# CrashButtonESP8266.net
KiCad netlist of a schematic drawn in EAGLE
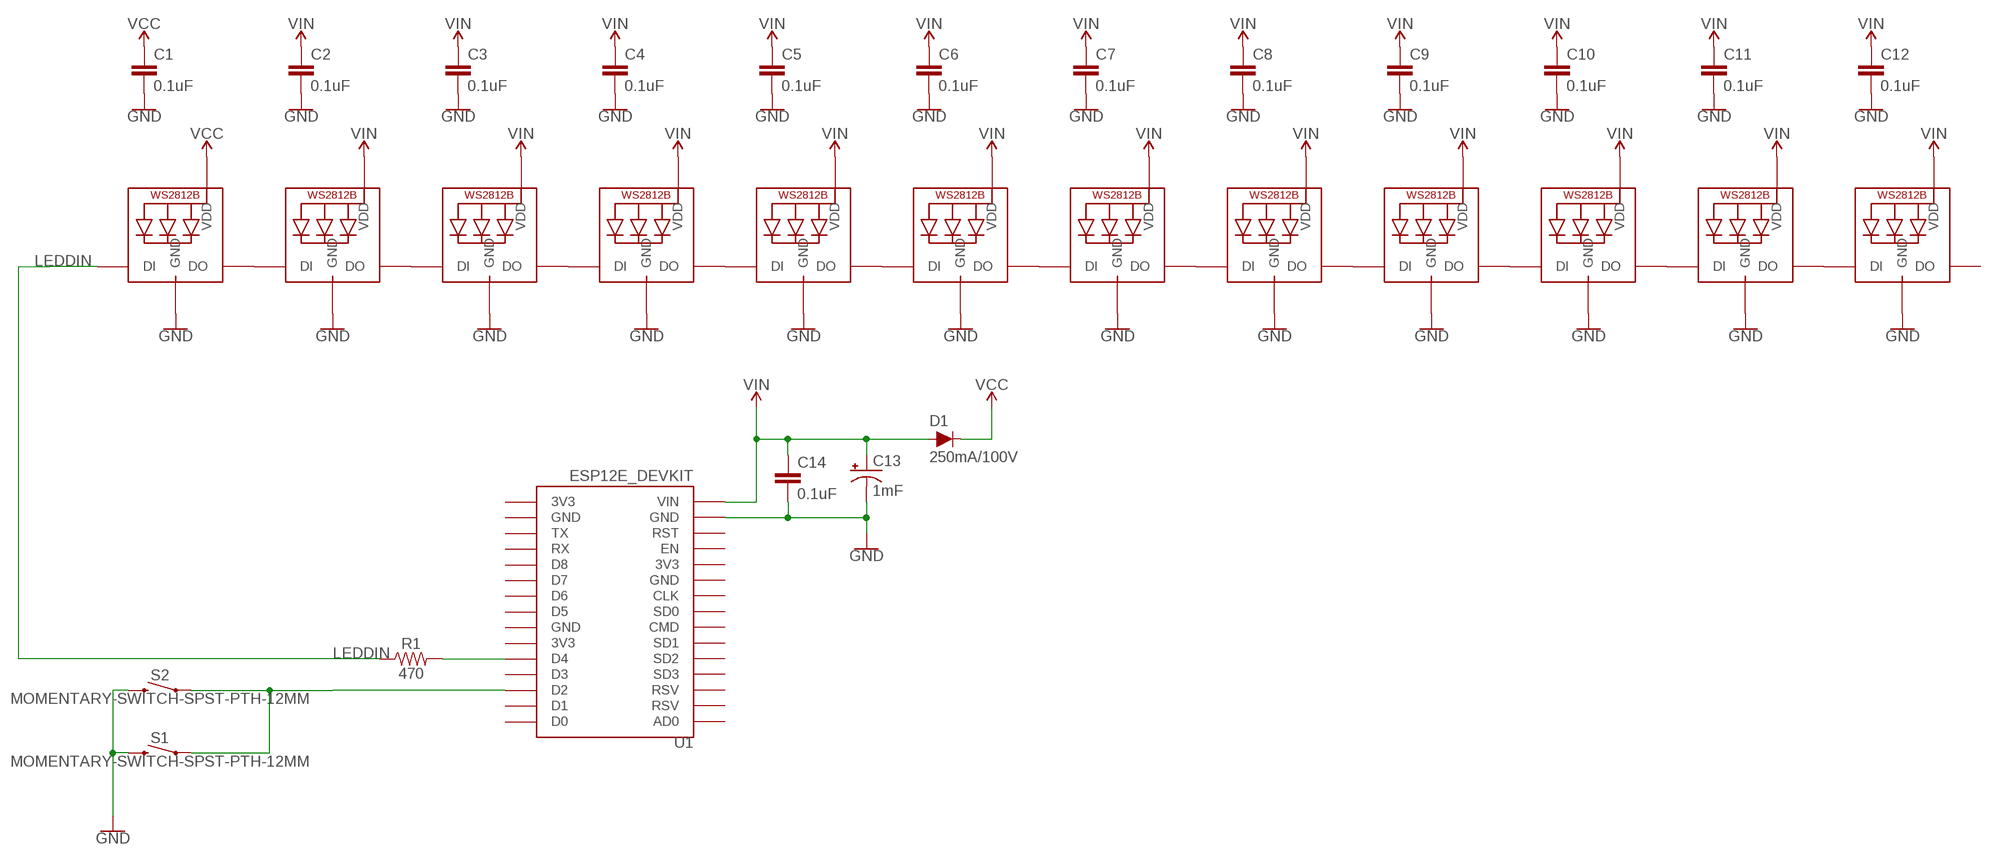
[diagram p0: schematic, sheet 1]

(export (version "E")
  (design (tool "Eeschema 10.0.6"))
  (components
    (comp (ref "C1")
      (value "0.1uF")
      (footprint "eagle-import:0603")
      (libsource (lib "eagle-import") (part "0.1UF-0603-25V-(+80/-20%)"))
    )
    (comp (ref "C2")
      (value "0.1uF")
      (footprint "eagle-import:0603")
      (libsource (lib "eagle-import") (part "0.1UF-0603-25V-(+80/-20%)"))
    )
    (comp (ref "C3")
      (value "0.1uF")
      (footprint "eagle-import:0603")
      (libsource (lib "eagle-import") (part "0.1UF-0603-25V-(+80/-20%)"))
    )
    (comp (ref "C4")
      (value "0.1uF")
      (footprint "eagle-import:0603")
      (libsource (lib "eagle-import") (part "0.1UF-0603-25V-(+80/-20%)"))
    )
    (comp (ref "C5")
      (value "0.1uF")
      (footprint "eagle-import:0603")
      (libsource (lib "eagle-import") (part "0.1UF-0603-25V-(+80/-20%)"))
    )
    (comp (ref "C6")
      (value "0.1uF")
      (footprint "eagle-import:0603")
      (libsource (lib "eagle-import") (part "0.1UF-0603-25V-(+80/-20%)"))
    )
    (comp (ref "C7")
      (value "0.1uF")
      (footprint "eagle-import:0603")
      (libsource (lib "eagle-import") (part "0.1UF-0603-25V-(+80/-20%)"))
    )
    (comp (ref "C8")
      (value "0.1uF")
      (footprint "eagle-import:0603")
      (libsource (lib "eagle-import") (part "0.1UF-0603-25V-(+80/-20%)"))
    )
    (comp (ref "C9")
      (value "0.1uF")
      (footprint "eagle-import:0603")
      (libsource (lib "eagle-import") (part "0.1UF-0603-25V-(+80/-20%)"))
    )
    (comp (ref "C10")
      (value "0.1uF")
      (footprint "eagle-import:0603")
      (libsource (lib "eagle-import") (part "0.1UF-0603-25V-(+80/-20%)"))
    )
    (comp (ref "C11")
      (value "0.1uF")
      (footprint "eagle-import:0603")
      (libsource (lib "eagle-import") (part "0.1UF-0603-25V-(+80/-20%)"))
    )
    (comp (ref "C12")
      (value "0.1uF")
      (footprint "eagle-import:0603")
      (libsource (lib "eagle-import") (part "0.1UF-0603-25V-(+80/-20%)"))
    )
    (comp (ref "C13")
      (value "1mF")
      (footprint "eagle-import:CPOL-RADIAL-5MM-10MM")
      (libsource (lib "eagle-import") (part "1000UF-RADIAL-5MM-25V-20%"))
    )
    (comp (ref "C14")
      (value "0.1uF")
      (footprint "eagle-import:0603")
      (libsource (lib "eagle-import") (part "0.1UF-0603-25V-(+80/-20%)"))
    )
    (comp (ref "D1")
      (value "250mA/100V")
      (footprint "eagle-import:SOD-323")
      (libsource (lib "eagle-import") (part "DIODE-BAS16J"))
    )
    (comp (ref "LED1")
      (value "WS2812B5050")
      (footprint "eagle-import:WS2812B")
      (libsource (lib "eagle-import") (part "WS2812B5050"))
    )
    (comp (ref "LED2")
      (value "WS2812B5050")
      (footprint "eagle-import:WS2812B")
      (libsource (lib "eagle-import") (part "WS2812B5050"))
    )
    (comp (ref "LED3")
      (value "WS2812B5050")
      (footprint "eagle-import:WS2812B")
      (libsource (lib "eagle-import") (part "WS2812B5050"))
    )
    (comp (ref "LED4")
      (value "WS2812B5050")
      (footprint "eagle-import:WS2812B")
      (libsource (lib "eagle-import") (part "WS2812B5050"))
    )
    (comp (ref "LED5")
      (value "WS2812B5050")
      (footprint "eagle-import:WS2812B")
      (libsource (lib "eagle-import") (part "WS2812B5050"))
    )
    (comp (ref "LED6")
      (value "WS2812B5050")
      (footprint "eagle-import:WS2812B")
      (libsource (lib "eagle-import") (part "WS2812B5050"))
    )
    (comp (ref "LED7")
      (value "WS2812B5050")
      (footprint "eagle-import:WS2812B")
      (libsource (lib "eagle-import") (part "WS2812B5050"))
    )
    (comp (ref "LED8")
      (value "WS2812B5050")
      (footprint "eagle-import:WS2812B")
      (libsource (lib "eagle-import") (part "WS2812B5050"))
    )
    (comp (ref "LED9")
      (value "WS2812B5050")
      (footprint "eagle-import:WS2812B")
      (libsource (lib "eagle-import") (part "WS2812B5050"))
    )
    (comp (ref "LED10")
      (value "WS2812B5050")
      (footprint "eagle-import:WS2812B")
      (libsource (lib "eagle-import") (part "WS2812B5050"))
    )
    (comp (ref "LED11")
      (value "WS2812B5050")
      (footprint "eagle-import:WS2812B")
      (libsource (lib "eagle-import") (part "WS2812B5050"))
    )
    (comp (ref "LED12")
      (value "WS2812B5050")
      (footprint "eagle-import:WS2812B")
      (libsource (lib "eagle-import") (part "WS2812B5050"))
    )
    (comp (ref "R1")
      (value "470")
      (footprint "eagle-import:0603")
      (libsource (lib "eagle-import") (part "470OHM-0603-1/10W-1%"))
    )
    (comp (ref "S1")
      (value "MOMENTARY-SWITCH-SPST-PTH-12MM")
      (footprint "eagle-import:TACTILE_SWITCH_PTH_12MM")
      (libsource (lib "eagle-import") (part "MOMENTARY-SWITCH-SPST-PTH-12MM"))
    )
    (comp (ref "S2")
      (value "MOMENTARY-SWITCH-SPST-PTH-12MM")
      (footprint "eagle-import:TACTILE_SWITCH_PTH_12MM")
      (libsource (lib "eagle-import") (part "MOMENTARY-SWITCH-SPST-PTH-12MM"))
    )
    (comp (ref "U1")
      (value "ESP12E_DEVKIT")
      (footprint "eagle-import:ESP12E_DEVKIT")
      (libsource (lib "eagle-import") (part "ESP12E_DEVKIT"))
    )
  )
  (nets
    (net (code "1") (name "/LEDDIN") (class "Default")
      (node (ref "LED1") (pin "4-DIN") (pinfunction "DI_4-DIN") (pintype "input"))
      (node (ref "R1") (pin "1") (pinfunction "1_1") (pintype "passive"))
    )
    (net (code "2") (name "GND") (class "Default")
      (node (ref "C1") (pin "2") (pinfunction "2_2") (pintype "passive"))
      (node (ref "C10") (pin "2") (pinfunction "2_2") (pintype "passive"))
      (node (ref "C11") (pin "2") (pinfunction "2_2") (pintype "passive"))
      (node (ref "C12") (pin "2") (pinfunction "2_2") (pintype "passive"))
      (node (ref "C13") (pin "-") (pinfunction "-_-") (pintype "passive"))
      (node (ref "C14") (pin "2") (pinfunction "2_2") (pintype "passive"))
      (node (ref "C2") (pin "2") (pinfunction "2_2") (pintype "passive"))
      (node (ref "C3") (pin "2") (pinfunction "2_2") (pintype "passive"))
      (node (ref "C4") (pin "2") (pinfunction "2_2") (pintype "passive"))
      (node (ref "C5") (pin "2") (pinfunction "2_2") (pintype "passive"))
      (node (ref "C6") (pin "2") (pinfunction "2_2") (pintype "passive"))
      (node (ref "C7") (pin "2") (pinfunction "2_2") (pintype "passive"))
      (node (ref "C8") (pin "2") (pinfunction "2_2") (pintype "passive"))
      (node (ref "C9") (pin "2") (pinfunction "2_2") (pintype "passive"))
      (node (ref "LED1") (pin "3-GND") (pinfunction "GND_3-GND") (pintype "power_in"))
      (node (ref "LED10") (pin "3-GND") (pinfunction "GND_3-GND") (pintype "power_in"))
      (node (ref "LED11") (pin "3-GND") (pinfunction "GND_3-GND") (pintype "power_in"))
      (node (ref "LED12") (pin "3-GND") (pinfunction "GND_3-GND") (pintype "power_in"))
      (node (ref "LED2") (pin "3-GND") (pinfunction "GND_3-GND") (pintype "power_in"))
      (node (ref "LED3") (pin "3-GND") (pinfunction "GND_3-GND") (pintype "power_in"))
      (node (ref "LED4") (pin "3-GND") (pinfunction "GND_3-GND") (pintype "power_in"))
      (node (ref "LED5") (pin "3-GND") (pinfunction "GND_3-GND") (pintype "power_in"))
      (node (ref "LED6") (pin "3-GND") (pinfunction "GND_3-GND") (pintype "power_in"))
      (node (ref "LED7") (pin "3-GND") (pinfunction "GND_3-GND") (pintype "power_in"))
      (node (ref "LED8") (pin "3-GND") (pinfunction "GND_3-GND") (pintype "power_in"))
      (node (ref "LED9") (pin "3-GND") (pinfunction "GND_3-GND") (pintype "power_in"))
      (node (ref "S1") (pin "3") (pinfunction "2_3") (pintype "passive"))
      (node (ref "S2") (pin "3") (pinfunction "2_3") (pintype "passive"))
      (node (ref "U1") (pin "GND@1") (pinfunction "GND_GND@1") (pintype "bidirectional"))
    )
    (net (code "3") (name "Net-(LED1-DO)") (class "Default")
      (node (ref "LED1") (pin "2-DOUT") (pinfunction "DO_2-DOUT") (pintype "output"))
      (node (ref "LED2") (pin "4-DIN") (pinfunction "DI_4-DIN") (pintype "input"))
    )
    (net (code "4") (name "Net-(LED2-DO)") (class "Default")
      (node (ref "LED2") (pin "2-DOUT") (pinfunction "DO_2-DOUT") (pintype "output"))
      (node (ref "LED3") (pin "4-DIN") (pinfunction "DI_4-DIN") (pintype "input"))
    )
    (net (code "5") (name "Net-(LED3-DO)") (class "Default")
      (node (ref "LED3") (pin "2-DOUT") (pinfunction "DO_2-DOUT") (pintype "output"))
      (node (ref "LED4") (pin "4-DIN") (pinfunction "DI_4-DIN") (pintype "input"))
    )
    (net (code "6") (name "Net-(LED4-DO)") (class "Default")
      (node (ref "LED4") (pin "2-DOUT") (pinfunction "DO_2-DOUT") (pintype "output"))
      (node (ref "LED5") (pin "4-DIN") (pinfunction "DI_4-DIN") (pintype "input"))
    )
    (net (code "7") (name "Net-(LED5-DO)") (class "Default")
      (node (ref "LED5") (pin "2-DOUT") (pinfunction "DO_2-DOUT") (pintype "output"))
      (node (ref "LED6") (pin "4-DIN") (pinfunction "DI_4-DIN") (pintype "input"))
    )
    (net (code "8") (name "Net-(LED6-DO)") (class "Default")
      (node (ref "LED6") (pin "2-DOUT") (pinfunction "DO_2-DOUT") (pintype "output"))
      (node (ref "LED7") (pin "4-DIN") (pinfunction "DI_4-DIN") (pintype "input"))
    )
    (net (code "9") (name "Net-(LED7-DO)") (class "Default")
      (node (ref "LED7") (pin "2-DOUT") (pinfunction "DO_2-DOUT") (pintype "output"))
      (node (ref "LED8") (pin "4-DIN") (pinfunction "DI_4-DIN") (pintype "input"))
    )
    (net (code "10") (name "Net-(LED8-DO)") (class "Default")
      (node (ref "LED8") (pin "2-DOUT") (pinfunction "DO_2-DOUT") (pintype "output"))
      (node (ref "LED9") (pin "4-DIN") (pinfunction "DI_4-DIN") (pintype "input"))
    )
    (net (code "11") (name "Net-(LED10-DI)") (class "Default")
      (node (ref "LED10") (pin "4-DIN") (pinfunction "DI_4-DIN") (pintype "input"))
      (node (ref "LED9") (pin "2-DOUT") (pinfunction "DO_2-DOUT") (pintype "output"))
    )
    (net (code "12") (name "Net-(LED10-DO)") (class "Default")
      (node (ref "LED10") (pin "2-DOUT") (pinfunction "DO_2-DOUT") (pintype "output"))
      (node (ref "LED11") (pin "4-DIN") (pinfunction "DI_4-DIN") (pintype "input"))
    )
    (net (code "13") (name "Net-(LED11-DO)") (class "Default")
      (node (ref "LED11") (pin "2-DOUT") (pinfunction "DO_2-DOUT") (pintype "output"))
      (node (ref "LED12") (pin "4-DIN") (pinfunction "DI_4-DIN") (pintype "input"))
    )
    (net (code "14") (name "Net-(R1-Pad2)") (class "Default")
      (node (ref "R1") (pin "2") (pinfunction "2_2") (pintype "passive"))
      (node (ref "U1") (pin "D4") (pinfunction "D4_D4") (pintype "bidirectional"))
    )
    (net (code "15") (name "Net-(S1-Pad1)") (class "Default")
      (node (ref "S1") (pin "1") (pinfunction "1_1") (pintype "passive"))
      (node (ref "S2") (pin "1") (pinfunction "1_1") (pintype "passive"))
      (node (ref "U1") (pin "D2") (pinfunction "D2_D2") (pintype "bidirectional"))
    )
    (net (code "16") (name "VCC") (class "Default")
      (node (ref "C1") (pin "1") (pinfunction "1_1") (pintype "passive"))
      (node (ref "D1") (pin "C") (pinfunction "C_C") (pintype "passive"))
      (node (ref "LED1") (pin "1-VDD") (pinfunction "VDD_1-VDD") (pintype "power_in"))
    )
    (net (code "17") (name "VIN") (class "Default")
      (node (ref "C10") (pin "1") (pinfunction "1_1") (pintype "passive"))
      (node (ref "C11") (pin "1") (pinfunction "1_1") (pintype "passive"))
      (node (ref "C12") (pin "1") (pinfunction "1_1") (pintype "passive"))
      (node (ref "C13") (pin "+") (pinfunction "+_+") (pintype "passive"))
      (node (ref "C14") (pin "1") (pinfunction "1_1") (pintype "passive"))
      (node (ref "C2") (pin "1") (pinfunction "1_1") (pintype "passive"))
      (node (ref "C3") (pin "1") (pinfunction "1_1") (pintype "passive"))
      (node (ref "C4") (pin "1") (pinfunction "1_1") (pintype "passive"))
      (node (ref "C5") (pin "1") (pinfunction "1_1") (pintype "passive"))
      (node (ref "C6") (pin "1") (pinfunction "1_1") (pintype "passive"))
      (node (ref "C7") (pin "1") (pinfunction "1_1") (pintype "passive"))
      (node (ref "C8") (pin "1") (pinfunction "1_1") (pintype "passive"))
      (node (ref "C9") (pin "1") (pinfunction "1_1") (pintype "passive"))
      (node (ref "D1") (pin "A") (pinfunction "A_A") (pintype "passive"))
      (node (ref "LED10") (pin "1-VDD") (pinfunction "VDD_1-VDD") (pintype "power_in"))
      (node (ref "LED11") (pin "1-VDD") (pinfunction "VDD_1-VDD") (pintype "power_in"))
      (node (ref "LED12") (pin "1-VDD") (pinfunction "VDD_1-VDD") (pintype "power_in"))
      (node (ref "LED2") (pin "1-VDD") (pinfunction "VDD_1-VDD") (pintype "power_in"))
      (node (ref "LED3") (pin "1-VDD") (pinfunction "VDD_1-VDD") (pintype "power_in"))
      (node (ref "LED4") (pin "1-VDD") (pinfunction "VDD_1-VDD") (pintype "power_in"))
      (node (ref "LED5") (pin "1-VDD") (pinfunction "VDD_1-VDD") (pintype "power_in"))
      (node (ref "LED6") (pin "1-VDD") (pinfunction "VDD_1-VDD") (pintype "power_in"))
      (node (ref "LED7") (pin "1-VDD") (pinfunction "VDD_1-VDD") (pintype "power_in"))
      (node (ref "LED8") (pin "1-VDD") (pinfunction "VDD_1-VDD") (pintype "power_in"))
      (node (ref "LED9") (pin "1-VDD") (pinfunction "VDD_1-VDD") (pintype "power_in"))
      (node (ref "U1") (pin "VIN") (pinfunction "VIN_VIN") (pintype "bidirectional"))
    )
    (net (code "18") (name "unconnected-(LED12-DO-Pad2-DOUT)") (class "Default")
      (node (ref "LED12") (pin "2-DOUT") (pinfunction "DO_2-DOUT") (pintype "output"))
    )
    (net (code "19") (name "unconnected-(U1-3V3-Pad3V3@0)") (class "Default")
      (node (ref "U1") (pin "3V3@0") (pinfunction "3V3_3V3@0") (pintype "bidirectional"))
    )
    (net (code "20") (name "unconnected-(U1-3V3-Pad3V3@1)") (class "Default")
      (node (ref "U1") (pin "3V3@1") (pinfunction "3V3_3V3@1") (pintype "bidirectional"))
    )
    (net (code "21") (name "unconnected-(U1-3V3-Pad3V3@2)") (class "Default")
      (node (ref "U1") (pin "3V3@2") (pinfunction "3V3_3V3@2") (pintype "bidirectional"))
    )
    (net (code "22") (name "unconnected-(U1-GND-PadGND@0)") (class "Default")
      (node (ref "U1") (pin "GND@0") (pinfunction "GND_GND@0") (pintype "bidirectional"))
    )
    (net (code "23") (name "unconnected-(U1-GND-PadGND@2)") (class "Default")
      (node (ref "U1") (pin "GND@2") (pinfunction "GND_GND@2") (pintype "bidirectional"))
    )
    (net (code "24") (name "unconnected-(U1-GND-PadGND@3)") (class "Default")
      (node (ref "U1") (pin "GND@3") (pinfunction "GND_GND@3") (pintype "bidirectional"))
    )
    (net (code "25") (name "unconnected-(U1-PadAD0)") (class "Default")
      (node (ref "U1") (pin "AD0") (pinfunction "AD0_AD0") (pintype "bidirectional"))
    )
    (net (code "26") (name "unconnected-(U1-PadCLK)") (class "Default")
      (node (ref "U1") (pin "CLK") (pinfunction "CLK_CLK") (pintype "bidirectional"))
    )
    (net (code "27") (name "unconnected-(U1-PadCMD)") (class "Default")
      (node (ref "U1") (pin "CMD") (pinfunction "CMD_CMD") (pintype "bidirectional"))
    )
    (net (code "28") (name "unconnected-(U1-PadD0)") (class "Default")
      (node (ref "U1") (pin "D0") (pinfunction "D0_D0") (pintype "bidirectional"))
    )
    (net (code "29") (name "unconnected-(U1-PadD1)") (class "Default")
      (node (ref "U1") (pin "D1") (pinfunction "D1_D1") (pintype "bidirectional"))
    )
    (net (code "30") (name "unconnected-(U1-PadD3)") (class "Default")
      (node (ref "U1") (pin "D3") (pinfunction "D3_D3") (pintype "bidirectional"))
    )
    (net (code "31") (name "unconnected-(U1-PadD5)") (class "Default")
      (node (ref "U1") (pin "D5") (pinfunction "D5_D5") (pintype "bidirectional"))
    )
    (net (code "32") (name "unconnected-(U1-PadD6)") (class "Default")
      (node (ref "U1") (pin "D6") (pinfunction "D6_D6") (pintype "bidirectional"))
    )
    (net (code "33") (name "unconnected-(U1-PadD7)") (class "Default")
      (node (ref "U1") (pin "D7") (pinfunction "D7_D7") (pintype "bidirectional"))
    )
    (net (code "34") (name "unconnected-(U1-PadD8)") (class "Default")
      (node (ref "U1") (pin "D8") (pinfunction "D8_D8") (pintype "bidirectional"))
    )
    (net (code "35") (name "unconnected-(U1-PadEN)") (class "Default")
      (node (ref "U1") (pin "EN") (pinfunction "EN_EN") (pintype "bidirectional"))
    )
    (net (code "36") (name "unconnected-(U1-PadRST)") (class "Default")
      (node (ref "U1") (pin "RST") (pinfunction "RST_RST") (pintype "bidirectional"))
    )
    (net (code "37") (name "unconnected-(U1-PadRX)") (class "Default")
      (node (ref "U1") (pin "RX") (pinfunction "RX_RX") (pintype "bidirectional"))
    )
    (net (code "38") (name "unconnected-(U1-PadSD0)") (class "Default")
      (node (ref "U1") (pin "SD0") (pinfunction "SD0_SD0") (pintype "bidirectional"))
    )
    (net (code "39") (name "unconnected-(U1-PadSD1)") (class "Default")
      (node (ref "U1") (pin "SD1") (pinfunction "SD1_SD1") (pintype "bidirectional"))
    )
    (net (code "40") (name "unconnected-(U1-PadSD2)") (class "Default")
      (node (ref "U1") (pin "SD2") (pinfunction "SD2_SD2") (pintype "bidirectional"))
    )
    (net (code "41") (name "unconnected-(U1-PadSD3)") (class "Default")
      (node (ref "U1") (pin "SD3") (pinfunction "SD3_SD3") (pintype "bidirectional"))
    )
    (net (code "42") (name "unconnected-(U1-PadTX)") (class "Default")
      (node (ref "U1") (pin "TX") (pinfunction "TX_TX") (pintype "bidirectional"))
    )
    (net (code "43") (name "unconnected-(U1-RSV-PadRSV@0)") (class "Default")
      (node (ref "U1") (pin "RSV@0") (pinfunction "RSV_RSV@0") (pintype "bidirectional"))
    )
    (net (code "44") (name "unconnected-(U1-RSV-PadRSV@1)") (class "Default")
      (node (ref "U1") (pin "RSV@1") (pinfunction "RSV_RSV@1") (pintype "bidirectional"))
    )
  )
)
